# Switches.net
KiCad netlist of a schematic drawn in Altium Designer
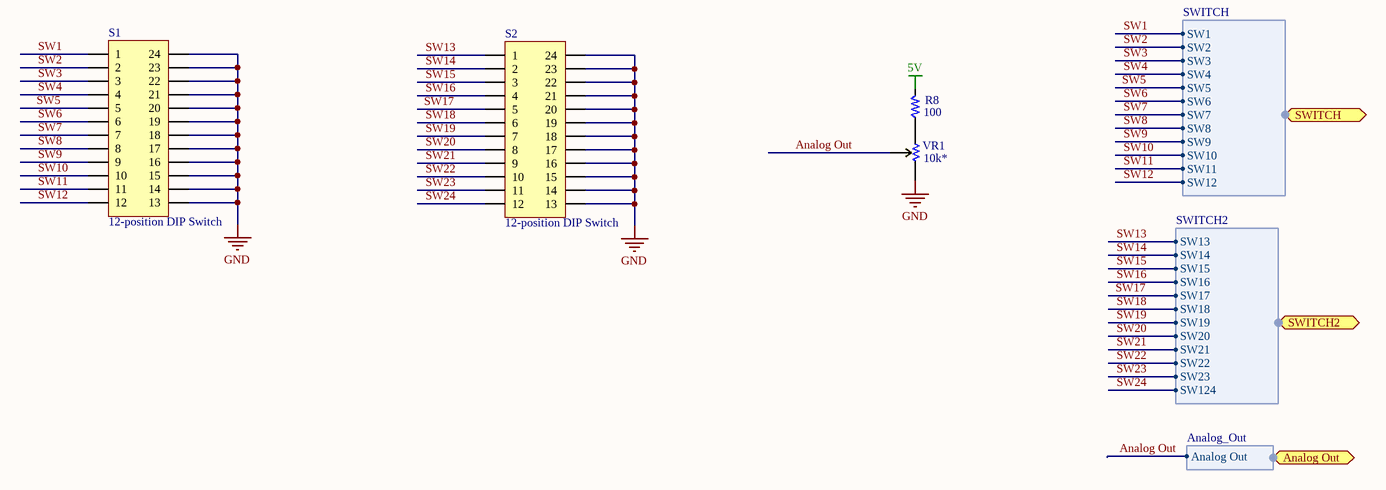
[diagram p0: Switches.SchDoc]

(export (version "E")
  (design (tool "Eeschema 10.0.6"))
  (components
    (comp (ref "R8")
      (value "SCH_GENERIC_RESISTOR_0603")
      (footprint "PCB_GENERIC_SMD_0603")
      (description "Generic SMD resistor 0603")
      (fields (field (name "RESISTANCE") "100"))
      (libsource (lib "Generic 0603 Resistor") (part "SCH_GENERIC_RESISTOR_0603"))
    )
    (comp (ref "S1")
      (value "12-position DIP Switch")
      (footprint "12-Position DIP Switch")
      (fields (field (name "MANUFACTURER") "CTS Electronics"))
      (libsource (lib "CTS 12-Position DIP Switch") (part "12-position DIP Switch"))
    )
    (comp (ref "S2")
      (value "12-position DIP Switch")
      (footprint "12-Position DIP Switch")
      (fields (field (name "MANUFACTURER") "CTS Electronics"))
      (libsource (lib "CTS 12-Position DIP Switch") (part "12-position DIP Switch"))
    )
    (comp (ref "VR1")
      (value "10k*")
      (footprint "Rotary Pot")
      (fields (field (name "TOLERANCE") "20%") (field (name "MANUFACTURER") "CTS Electronics"))
      (libsource (lib "CTS Electronics Rotary Pot") (part "Rotary Pot"))
    )
  )
  (nets
    (net (code "4") (name "/Analog Out") (class "Default") (node (ref "VR1") (pin "2") (pintype "passive")))
    (net (code "5") (name "/SW1") (class "Default")
      (node (ref "S1") (pin "1") (pinfunction "1_1") (pintype "passive"))
    )
    (net (code "6") (name "/SW2") (class "Default")
      (node (ref "S1") (pin "2") (pinfunction "2_2") (pintype "passive"))
    )
    (net (code "7") (name "/SW3") (class "Default")
      (node (ref "S1") (pin "3") (pinfunction "3_3") (pintype "passive"))
    )
    (net (code "8") (name "/SW4") (class "Default")
      (node (ref "S1") (pin "4") (pinfunction "4_4") (pintype "passive"))
    )
    (net (code "9") (name "/SW5") (class "Default")
      (node (ref "S1") (pin "5") (pinfunction "5_5") (pintype "passive"))
    )
    (net (code "10") (name "/SW6") (class "Default")
      (node (ref "S1") (pin "6") (pinfunction "6_6") (pintype "passive"))
    )
    (net (code "11") (name "/SW7") (class "Default")
      (node (ref "S1") (pin "7") (pinfunction "7_7") (pintype "passive"))
    )
    (net (code "12") (name "/SW8") (class "Default")
      (node (ref "S1") (pin "8") (pinfunction "8_8") (pintype "passive"))
    )
    (net (code "13") (name "/SW9") (class "Default")
      (node (ref "S1") (pin "9") (pinfunction "9_9") (pintype "passive"))
    )
    (net (code "14") (name "/SW10") (class "Default")
      (node (ref "S1") (pin "10") (pinfunction "10_10") (pintype "passive"))
    )
    (net (code "15") (name "/SW11") (class "Default")
      (node (ref "S1") (pin "11") (pinfunction "11_11") (pintype "passive"))
    )
    (net (code "16") (name "/SW12") (class "Default")
      (node (ref "S1") (pin "12") (pinfunction "12_12") (pintype "passive"))
    )
    (net (code "17") (name "/SW13") (class "Default")
      (node (ref "S2") (pin "1") (pinfunction "1_1") (pintype "passive"))
    )
    (net (code "18") (name "/SW14") (class "Default")
      (node (ref "S2") (pin "2") (pinfunction "2_2") (pintype "passive"))
    )
    (net (code "19") (name "/SW15") (class "Default")
      (node (ref "S2") (pin "3") (pinfunction "3_3") (pintype "passive"))
    )
    (net (code "20") (name "/SW16") (class "Default")
      (node (ref "S2") (pin "4") (pinfunction "4_4") (pintype "passive"))
    )
    (net (code "21") (name "/SW17") (class "Default")
      (node (ref "S2") (pin "5") (pinfunction "5_5") (pintype "passive"))
    )
    (net (code "22") (name "/SW18") (class "Default")
      (node (ref "S2") (pin "6") (pinfunction "6_6") (pintype "passive"))
    )
    (net (code "23") (name "/SW19") (class "Default")
      (node (ref "S2") (pin "7") (pinfunction "7_7") (pintype "passive"))
    )
    (net (code "24") (name "/SW20") (class "Default")
      (node (ref "S2") (pin "8") (pinfunction "8_8") (pintype "passive"))
    )
    (net (code "25") (name "/SW21") (class "Default")
      (node (ref "S2") (pin "9") (pinfunction "9_9") (pintype "passive"))
    )
    (net (code "26") (name "/SW22") (class "Default")
      (node (ref "S2") (pin "10") (pinfunction "10_10") (pintype "passive"))
    )
    (net (code "27") (name "/SW23") (class "Default")
      (node (ref "S2") (pin "11") (pinfunction "11_11") (pintype "passive"))
    )
    (net (code "28") (name "/SW24") (class "Default")
      (node (ref "S2") (pin "12") (pinfunction "12_12") (pintype "passive"))
    )
    (net (code "32") (name "5V") (class "Default")
      (node (ref "R8") (pin "2") (pinfunction "2_2") (pintype "passive"))
    )
    (net (code "33") (name "GND") (class "Default")
      (node (ref "S1") (pin "13") (pinfunction "13_13") (pintype "passive"))
      (node (ref "S1") (pin "14") (pinfunction "14_14") (pintype "passive"))
      (node (ref "S1") (pin "15") (pinfunction "15_15") (pintype "passive"))
      (node (ref "S1") (pin "16") (pinfunction "16_16") (pintype "passive"))
      (node (ref "S1") (pin "17") (pinfunction "17_17") (pintype "passive"))
      (node (ref "S1") (pin "18") (pinfunction "18_18") (pintype "passive"))
      (node (ref "S1") (pin "19") (pinfunction "19_19") (pintype "passive"))
      (node (ref "S1") (pin "20") (pinfunction "20_20") (pintype "passive"))
      (node (ref "S1") (pin "21") (pinfunction "21_21") (pintype "passive"))
      (node (ref "S1") (pin "22") (pinfunction "22_22") (pintype "passive"))
      (node (ref "S1") (pin "23") (pinfunction "23_23") (pintype "passive"))
      (node (ref "S1") (pin "24") (pinfunction "24_24") (pintype "passive"))
      (node (ref "S2") (pin "13") (pinfunction "13_13") (pintype "passive"))
      (node (ref "S2") (pin "14") (pinfunction "14_14") (pintype "passive"))
      (node (ref "S2") (pin "15") (pinfunction "15_15") (pintype "passive"))
      (node (ref "S2") (pin "16") (pinfunction "16_16") (pintype "passive"))
      (node (ref "S2") (pin "17") (pinfunction "17_17") (pintype "passive"))
      (node (ref "S2") (pin "18") (pinfunction "18_18") (pintype "passive"))
      (node (ref "S2") (pin "19") (pinfunction "19_19") (pintype "passive"))
      (node (ref "S2") (pin "20") (pinfunction "20_20") (pintype "passive"))
      (node (ref "S2") (pin "21") (pinfunction "21_21") (pintype "passive"))
      (node (ref "S2") (pin "22") (pinfunction "22_22") (pintype "passive"))
      (node (ref "S2") (pin "23") (pinfunction "23_23") (pintype "passive"))
      (node (ref "S2") (pin "24") (pinfunction "24_24") (pintype "passive"))
      (node (ref "VR1") (pin "3") (pintype "passive"))
    )
    (net (code "34") (name "Net-(R8-Pad1)") (class "Default")
      (node (ref "R8") (pin "1") (pinfunction "1_1") (pintype "passive"))
      (node (ref "VR1") (pin "1") (pintype "passive"))
    )
  )
)
